# Sheet.net
KiCad netlist of a schematic drawn in Altium Designer
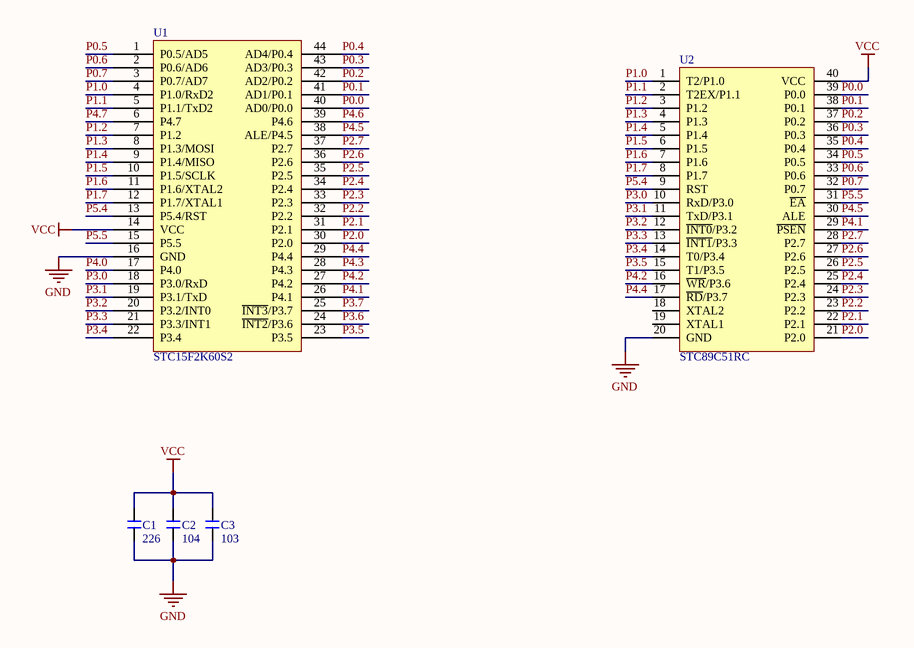
[diagram p0: Sheet.SchDoc]

(export (version "E")
  (design (tool "Eeschema 10.0.6"))
  (components
    (comp (ref "C1")
      (value "226")
      (footprint "C 1206_M")
      (description "无极性贴片电容")
      (fields (field (name "版权归属") "源创客"))
      (libsource (lib "3.1   - 电阻-电容-电感") (part "C"))
    )
    (comp (ref "C2")
      (value "104")
      (footprint "C 0805_L")
      (description "无极性贴片电容")
      (fields (field (name "版权归属") "源创客"))
      (libsource (lib "3.1   - 电阻-电容-电感") (part "C"))
    )
    (comp (ref "C3")
      (value "103")
      (footprint "C 0805_L")
      (description "无极性贴片电容")
      (fields (field (name "版权归属") "源创客"))
      (libsource (lib "3.1   - 电阻-电容-电感") (part "C"))
    )
    (comp (ref "U1")
      (value "STC15F2K60S2")
      (footprint "LQFP44 10X10_L")
      (description "STC单片机")
      (fields (field (name "版权归属") "源创客"))
      (libsource (lib "2.3   - STC系列单片机") (part "STC15F2K60S2-44pin"))
    )
    (comp (ref "U2")
      (value "STC89C51RC")
      (footprint "DIP40-600")
      (description "STC单片机")
      (fields (field (name "版权归属") "源创客"))
      (libsource (lib "2.3   - STC系列单片机") (part "STC89C51RC"))
    )
  )
  (nets
    (net (code "1") (name "/P0.0") (class "Default")
      (node (ref "U1") (pin "40") (pinfunction "AD0/P0.0_40") (pintype "passive"))
      (node (ref "U2") (pin "39") (pinfunction "P0.0_39") (pintype "passive"))
    )
    (net (code "2") (name "/P0.1") (class "Default")
      (node (ref "U1") (pin "41") (pinfunction "AD1/P0.1_41") (pintype "passive"))
      (node (ref "U2") (pin "38") (pinfunction "P0.1_38") (pintype "passive"))
    )
    (net (code "3") (name "/P0.2") (class "Default")
      (node (ref "U1") (pin "42") (pinfunction "AD2/P0.2_42") (pintype "passive"))
      (node (ref "U2") (pin "37") (pinfunction "P0.2_37") (pintype "passive"))
    )
    (net (code "4") (name "/P0.3") (class "Default")
      (node (ref "U1") (pin "43") (pinfunction "AD3/P0.3_43") (pintype "passive"))
      (node (ref "U2") (pin "36") (pinfunction "P0.3_36") (pintype "passive"))
    )
    (net (code "5") (name "/P0.4") (class "Default")
      (node (ref "U1") (pin "44") (pinfunction "AD4/P0.4_44") (pintype "passive"))
      (node (ref "U2") (pin "35") (pinfunction "P0.4_35") (pintype "passive"))
    )
    (net (code "6") (name "/P0.5") (class "Default")
      (node (ref "U1") (pin "1") (pinfunction "P0.5/AD5_1") (pintype "passive"))
      (node (ref "U2") (pin "34") (pinfunction "P0.5_34") (pintype "passive"))
    )
    (net (code "7") (name "/P0.6") (class "Default")
      (node (ref "U1") (pin "2") (pinfunction "P0.6/AD6_2") (pintype "passive"))
      (node (ref "U2") (pin "33") (pinfunction "P0.6_33") (pintype "passive"))
    )
    (net (code "8") (name "/P0.7") (class "Default")
      (node (ref "U1") (pin "3") (pinfunction "P0.7/AD7_3") (pintype "passive"))
      (node (ref "U2") (pin "32") (pinfunction "P0.7_32") (pintype "passive"))
    )
    (net (code "9") (name "/P1.0") (class "Default")
      (node (ref "U1") (pin "4") (pinfunction "P1.0/RxD2_4") (pintype "passive"))
      (node (ref "U2") (pin "1") (pinfunction "T2/P1.0_1") (pintype "passive"))
    )
    (net (code "10") (name "/P1.1") (class "Default")
      (node (ref "U1") (pin "5") (pinfunction "P1.1/TxD2_5") (pintype "passive"))
      (node (ref "U2") (pin "2") (pinfunction "T2EX/P1.1_2") (pintype "passive"))
    )
    (net (code "11") (name "/P1.2") (class "Default")
      (node (ref "U1") (pin "7") (pinfunction "P1.2_7") (pintype "passive"))
      (node (ref "U2") (pin "3") (pinfunction "P1.2_3") (pintype "passive"))
    )
    (net (code "12") (name "/P1.3") (class "Default")
      (node (ref "U1") (pin "8") (pinfunction "P1.3/MOSI_8") (pintype "passive"))
      (node (ref "U2") (pin "4") (pinfunction "P1.3_4") (pintype "passive"))
    )
    (net (code "13") (name "/P1.4") (class "Default")
      (node (ref "U1") (pin "9") (pinfunction "P1.4/MISO_9") (pintype "passive"))
      (node (ref "U2") (pin "5") (pinfunction "P1.4_5") (pintype "passive"))
    )
    (net (code "14") (name "/P1.5") (class "Default")
      (node (ref "U1") (pin "10") (pinfunction "P1.5/SCLK_10") (pintype "passive"))
      (node (ref "U2") (pin "6") (pinfunction "P1.5_6") (pintype "passive"))
    )
    (net (code "15") (name "/P1.6") (class "Default")
      (node (ref "U1") (pin "11") (pinfunction "P1.6/XTAL2_11") (pintype "passive"))
      (node (ref "U2") (pin "7") (pinfunction "P1.6_7") (pintype "passive"))
    )
    (net (code "16") (name "/P1.7") (class "Default")
      (node (ref "U1") (pin "12") (pinfunction "P1.7/XTAL1_12") (pintype "passive"))
      (node (ref "U2") (pin "8") (pinfunction "P1.7_8") (pintype "passive"))
    )
    (net (code "17") (name "/P2.0") (class "Default")
      (node (ref "U1") (pin "30") (pinfunction "P2.0_30") (pintype "passive"))
      (node (ref "U2") (pin "21") (pinfunction "P2.0_21") (pintype "passive"))
    )
    (net (code "18") (name "/P2.1") (class "Default")
      (node (ref "U1") (pin "31") (pinfunction "P2.1_31") (pintype "passive"))
      (node (ref "U2") (pin "22") (pinfunction "P2.1_22") (pintype "passive"))
    )
    (net (code "19") (name "/P2.2") (class "Default")
      (node (ref "U1") (pin "32") (pinfunction "P2.2_32") (pintype "passive"))
      (node (ref "U2") (pin "23") (pinfunction "P2.2_23") (pintype "passive"))
    )
    (net (code "20") (name "/P2.3") (class "Default")
      (node (ref "U1") (pin "33") (pinfunction "P2.3_33") (pintype "passive"))
      (node (ref "U2") (pin "24") (pinfunction "P2.3_24") (pintype "passive"))
    )
    (net (code "21") (name "/P2.4") (class "Default")
      (node (ref "U1") (pin "34") (pinfunction "P2.4_34") (pintype "passive"))
      (node (ref "U2") (pin "25") (pinfunction "P2.4_25") (pintype "passive"))
    )
    (net (code "22") (name "/P2.5") (class "Default")
      (node (ref "U1") (pin "35") (pinfunction "P2.5_35") (pintype "passive"))
      (node (ref "U2") (pin "26") (pinfunction "P2.5_26") (pintype "passive"))
    )
    (net (code "23") (name "/P2.6") (class "Default")
      (node (ref "U1") (pin "36") (pinfunction "P2.6_36") (pintype "passive"))
      (node (ref "U2") (pin "27") (pinfunction "P2.6_27") (pintype "passive"))
    )
    (net (code "24") (name "/P2.7") (class "Default")
      (node (ref "U1") (pin "37") (pinfunction "P2.7_37") (pintype "passive"))
      (node (ref "U2") (pin "28") (pinfunction "P2.7_28") (pintype "passive"))
    )
    (net (code "25") (name "/P3.0") (class "Default")
      (node (ref "U1") (pin "18") (pinfunction "P3.0/RxD_18") (pintype "passive"))
      (node (ref "U2") (pin "10") (pinfunction "RxD/P3.0_10") (pintype "passive"))
    )
    (net (code "26") (name "/P3.1") (class "Default")
      (node (ref "U1") (pin "19") (pinfunction "P3.1/TxD_19") (pintype "passive"))
      (node (ref "U2") (pin "11") (pinfunction "TxD/P3.1_11") (pintype "passive"))
    )
    (net (code "27") (name "/P3.2") (class "Default")
      (node (ref "U1") (pin "20") (pinfunction "P3.2/INT0_20") (pintype "passive"))
      (node (ref "U2") (pin "12") (pinfunction "~{INT0}/P3.2_12") (pintype "passive"))
    )
    (net (code "28") (name "/P3.3") (class "Default")
      (node (ref "U1") (pin "21") (pinfunction "P3.3/INT1_21") (pintype "passive"))
      (node (ref "U2") (pin "13") (pinfunction "~{INT1}/P3.3_13") (pintype "passive"))
    )
    (net (code "29") (name "/P3.4") (class "Default")
      (node (ref "U1") (pin "22") (pinfunction "P3.4_22") (pintype "passive"))
      (node (ref "U2") (pin "14") (pinfunction "T0/P3.4_14") (pintype "passive"))
    )
    (net (code "30") (name "/P3.5") (class "Default")
      (node (ref "U1") (pin "23") (pinfunction "P3.5_23") (pintype "passive"))
      (node (ref "U2") (pin "15") (pinfunction "T1/P3.5_15") (pintype "passive"))
    )
    (net (code "31") (name "/P3.6") (class "Default")
      (node (ref "U1") (pin "24") (pinfunction "~{INT2}/P3.6_24") (pintype "passive"))
    )
    (net (code "32") (name "/P3.7") (class "Default")
      (node (ref "U1") (pin "25") (pinfunction "~{INT3}/P3.7_25") (pintype "passive"))
    )
    (net (code "33") (name "/P4.0") (class "Default")
      (node (ref "U1") (pin "17") (pinfunction "P4.0_17") (pintype "passive"))
    )
    (net (code "34") (name "/P4.1") (class "Default")
      (node (ref "U1") (pin "26") (pinfunction "P4.1_26") (pintype "passive"))
      (node (ref "U2") (pin "29") (pinfunction "~{PSEN}_29") (pintype "passive"))
    )
    (net (code "35") (name "/P4.2") (class "Default")
      (node (ref "U1") (pin "27") (pinfunction "P4.2_27") (pintype "passive"))
      (node (ref "U2") (pin "16") (pinfunction "~{WR}/P3.6_16") (pintype "passive"))
    )
    (net (code "36") (name "/P4.3") (class "Default")
      (node (ref "U1") (pin "28") (pinfunction "P4.3_28") (pintype "passive"))
    )
    (net (code "37") (name "/P4.4") (class "Default")
      (node (ref "U1") (pin "29") (pinfunction "P4.4_29") (pintype "passive"))
      (node (ref "U2") (pin "17") (pinfunction "~{RD}/P3.7_17") (pintype "passive"))
    )
    (net (code "38") (name "/P4.5") (class "Default")
      (node (ref "U1") (pin "38") (pinfunction "ALE/P4.5_38") (pintype "passive"))
      (node (ref "U2") (pin "30") (pinfunction "ALE_30") (pintype "passive"))
    )
    (net (code "39") (name "/P4.6") (class "Default")
      (node (ref "U1") (pin "39") (pinfunction "P4.6_39") (pintype "passive"))
    )
    (net (code "40") (name "/P4.7") (class "Default")
      (node (ref "U1") (pin "6") (pinfunction "P4.7_6") (pintype "passive"))
    )
    (net (code "41") (name "/P5.4") (class "Default")
      (node (ref "U1") (pin "13") (pinfunction "P5.4/RST_13") (pintype "passive"))
      (node (ref "U2") (pin "9") (pinfunction "RST_9") (pintype "passive"))
    )
    (net (code "42") (name "/P5.5") (class "Default")
      (node (ref "U1") (pin "15") (pinfunction "P5.5_15") (pintype "passive"))
      (node (ref "U2") (pin "31") (pinfunction "~{EA}_31") (pintype "passive"))
    )
    (net (code "43") (name "GND") (class "Default")
      (node (ref "C1") (pin "1") (pinfunction "1_1") (pintype "passive"))
      (node (ref "C2") (pin "1") (pinfunction "1_1") (pintype "passive"))
      (node (ref "C3") (pin "1") (pinfunction "1_1") (pintype "passive"))
      (node (ref "U1") (pin "16") (pinfunction "GND_16") (pintype "passive"))
      (node (ref "U2") (pin "20") (pinfunction "GND_20") (pintype "passive"))
    )
    (net (code "44") (name "VCC") (class "Default")
      (node (ref "C1") (pin "2") (pinfunction "2_2") (pintype "passive"))
      (node (ref "C2") (pin "2") (pinfunction "2_2") (pintype "passive"))
      (node (ref "C3") (pin "2") (pinfunction "2_2") (pintype "passive"))
      (node (ref "U1") (pin "14") (pinfunction "VCC_14") (pintype "passive"))
      (node (ref "U2") (pin "40") (pinfunction "VCC_40") (pintype "passive"))
    )
    (net (code "45") (name "unconnected-(U2-XTAL1-Pad19)") (class "Default")
      (node (ref "U2") (pin "19") (pinfunction "XTAL1_19") (pintype "passive"))
    )
    (net (code "46") (name "unconnected-(U2-XTAL2-Pad18)") (class "Default")
      (node (ref "U2") (pin "18") (pinfunction "XTAL2_18") (pintype "passive"))
    )
  )
)
